# ionode.net
KiCad netlist of a schematic drawn in EAGLE
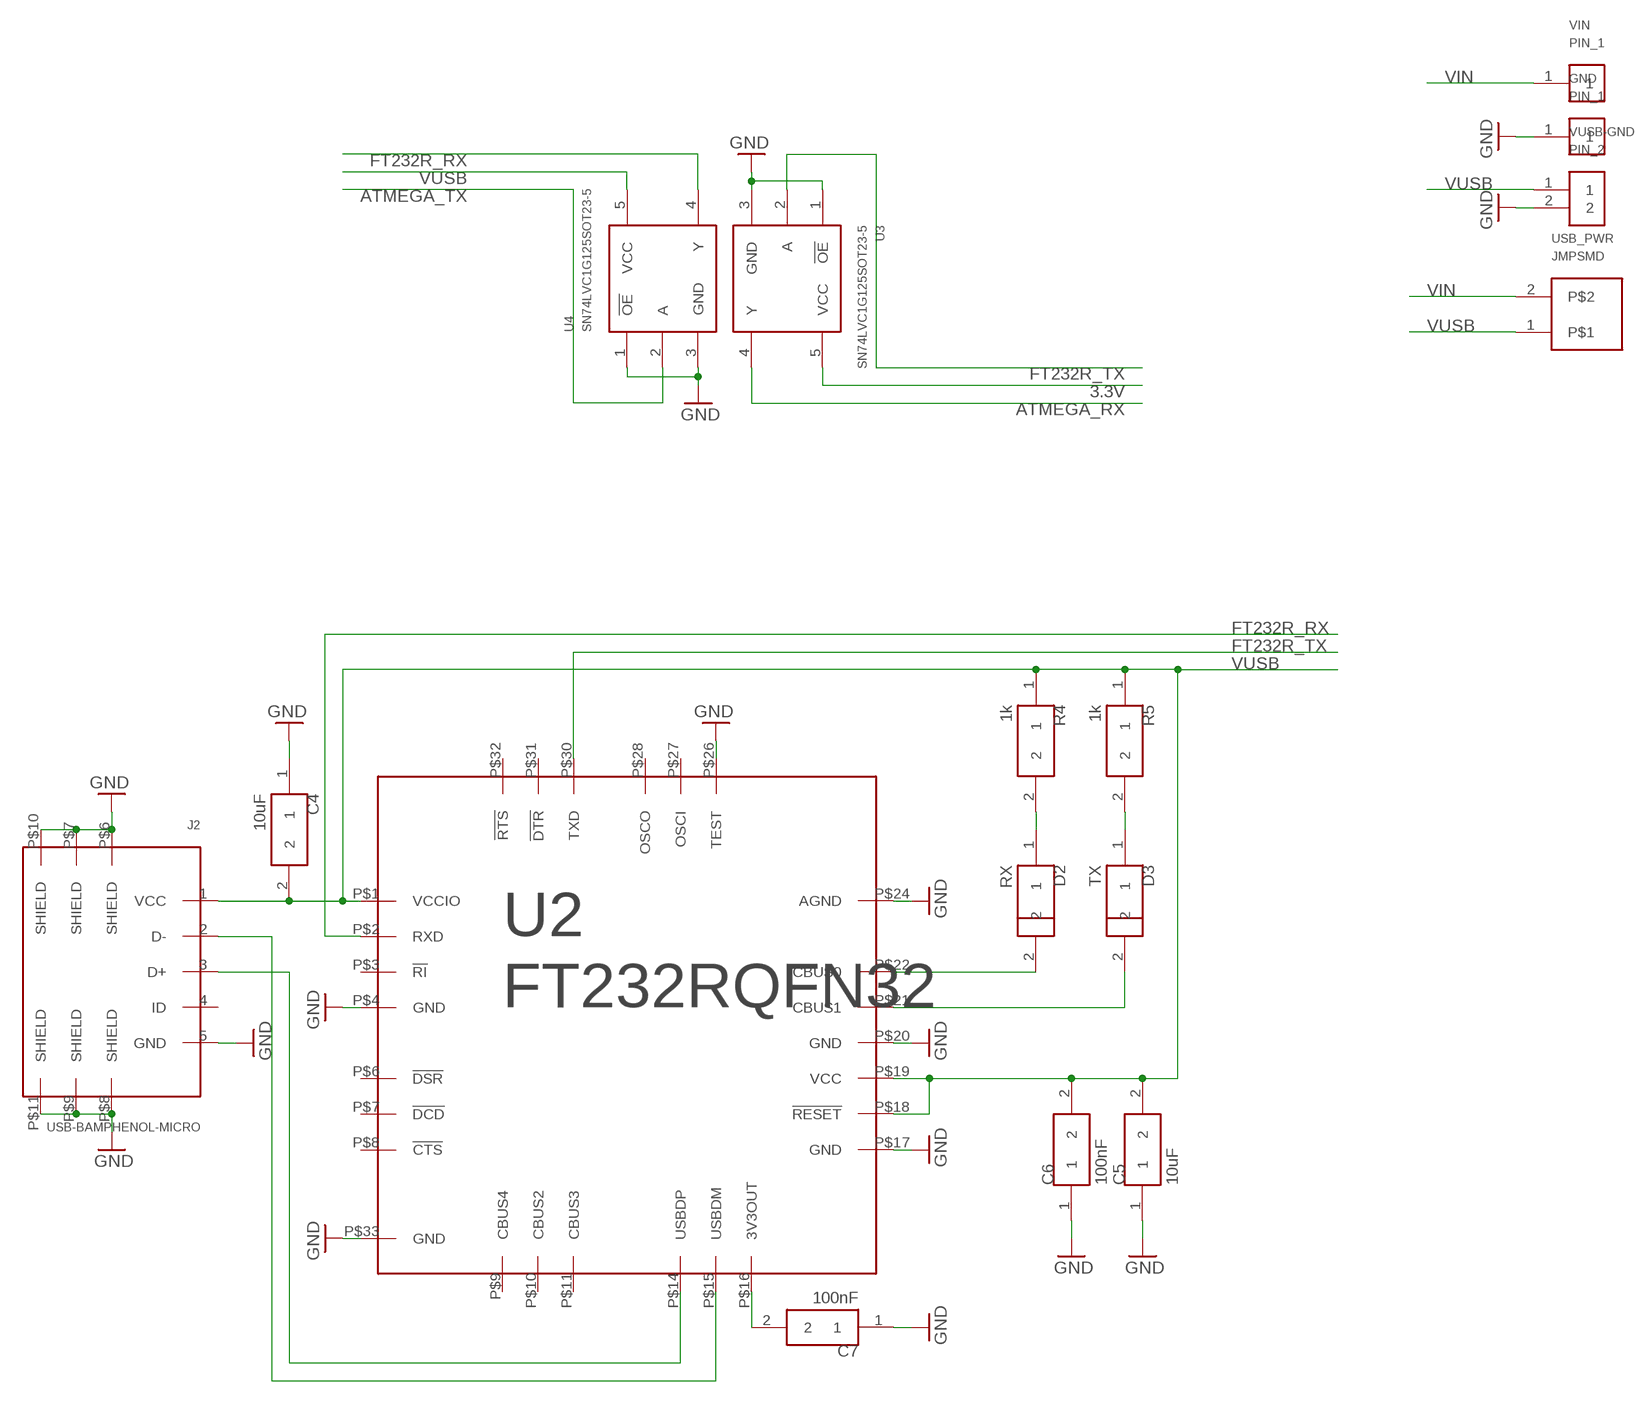
[diagram p0: schematic, sheet 1, part 1 of 2]
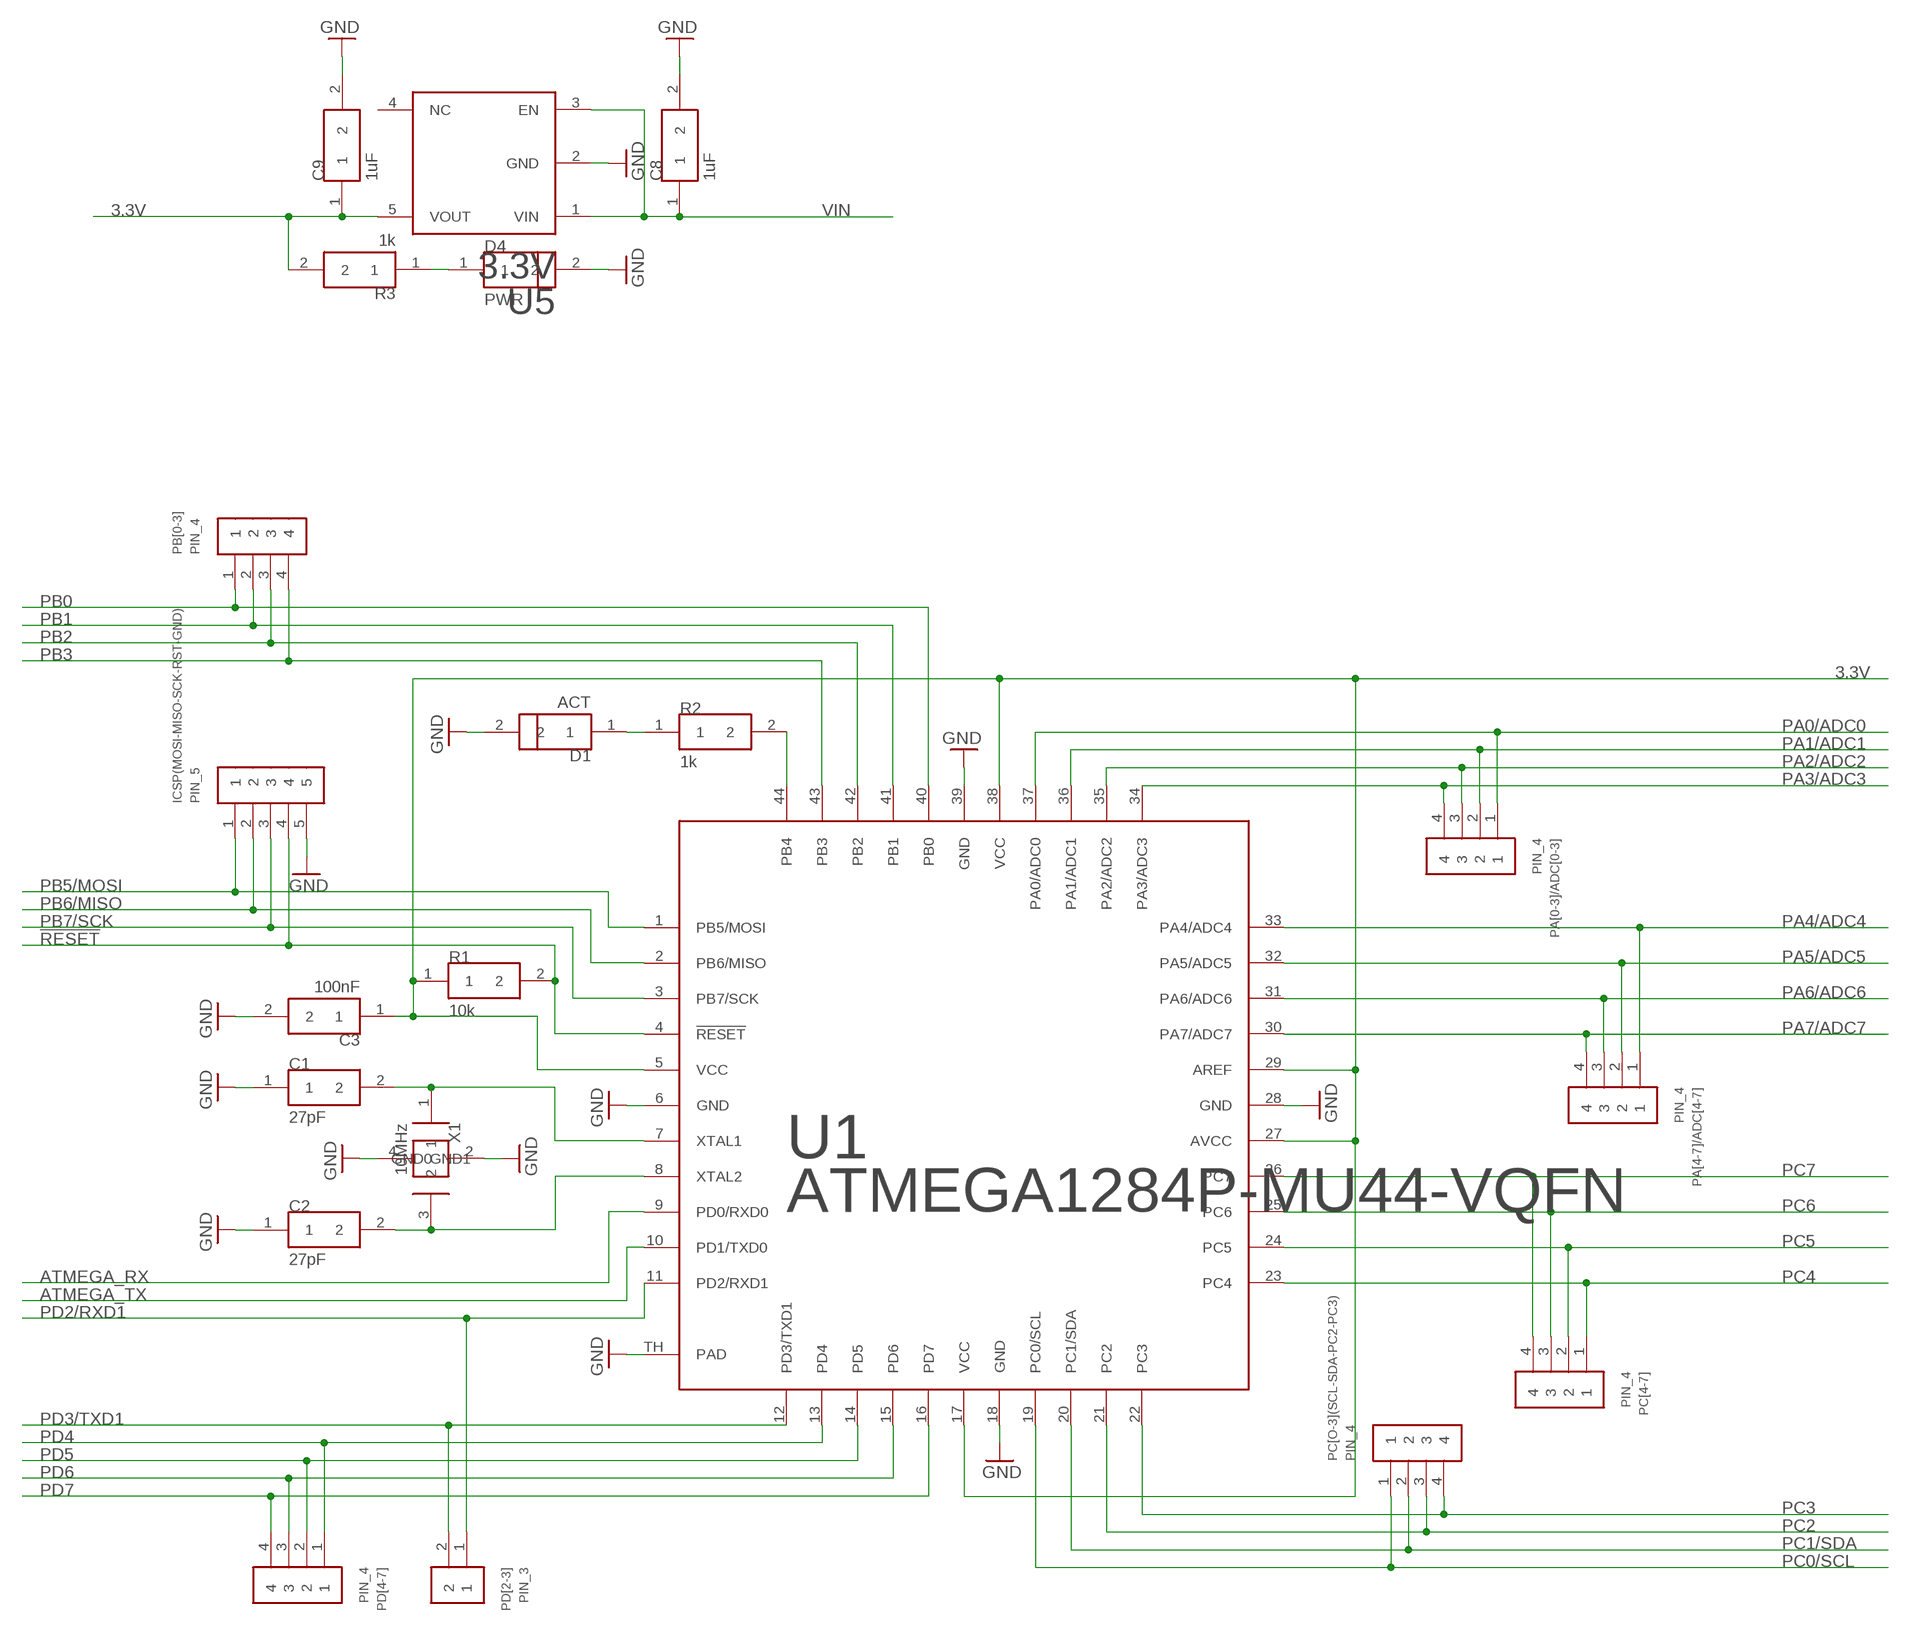
[diagram p1: schematic, sheet 1, part 2 of 2]

(export (version "E")
  (design (tool "Eeschema 10.0.6"))
  (components
    (comp (ref "C1")
      (value "27pF")
      (footprint "eagle-import:0402")
      (libsource (lib "eagle-import") (part "CAP0402"))
    )
    (comp (ref "C2")
      (value "27pF")
      (footprint "eagle-import:0402")
      (libsource (lib "eagle-import") (part "CAP0402"))
    )
    (comp (ref "C3")
      (value "100nF")
      (footprint "eagle-import:0402")
      (libsource (lib "eagle-import") (part "CAP0402"))
    )
    (comp (ref "C4")
      (value "10uF")
      (footprint "eagle-import:0805")
      (libsource (lib "eagle-import") (part "CAP0805"))
    )
    (comp (ref "C5")
      (value "10uF")
      (footprint "eagle-import:0805")
      (libsource (lib "eagle-import") (part "CAP0805"))
    )
    (comp (ref "C6")
      (value "100nF")
      (footprint "eagle-import:0402")
      (libsource (lib "eagle-import") (part "CAP0402"))
    )
    (comp (ref "C7")
      (value "100nF")
      (footprint "eagle-import:0402")
      (libsource (lib "eagle-import") (part "CAP0402"))
    )
    (comp (ref "C8")
      (value "1uF")
      (footprint "eagle-import:0402")
      (libsource (lib "eagle-import") (part "CAP0402"))
    )
    (comp (ref "C9")
      (value "1uF")
      (footprint "eagle-import:0402")
      (libsource (lib "eagle-import") (part "CAP0402"))
    )
    (comp (ref "D1")
      (value "ACT")
      (footprint "eagle-import:0402")
      (libsource (lib "eagle-import") (part "LED0402"))
    )
    (comp (ref "D2")
      (value "RX")
      (footprint "eagle-import:0402")
      (libsource (lib "eagle-import") (part "LED0402"))
    )
    (comp (ref "D3")
      (value "TX")
      (footprint "eagle-import:0402")
      (libsource (lib "eagle-import") (part "LED0402"))
    )
    (comp (ref "D4")
      (value "PWR")
      (footprint "eagle-import:0402")
      (libsource (lib "eagle-import") (part "LED0402"))
    )
    (comp (ref "GND")
      (value "PIN_1")
      (footprint "eagle-import:PIN_1")
      (libsource (lib "eagle-import") (part "PIN_1"))
    )
    (comp (ref "ICSP(MOSI-MISO-SCK-RST-GND)")
      (value "PIN_5")
      (footprint "eagle-import:PIN_5")
      (libsource (lib "eagle-import") (part "PIN_5"))
    )
    (comp (ref "J2")
      (value "USB-BAMPHENOL-MICRO")
      (footprint "eagle-import:AMPHENOL-USB-MICRO-B")
      (libsource (lib "eagle-import") (part "USB-BAMPHENOL-MICRO"))
    )
    (comp (ref "PA[0-3]/ADC[0-3]")
      (value "PIN_4")
      (footprint "eagle-import:PIN_4")
      (libsource (lib "eagle-import") (part "PIN_4"))
    )
    (comp (ref "PA[4-7]/ADC[4-7]")
      (value "PIN_4")
      (footprint "eagle-import:PIN_4")
      (libsource (lib "eagle-import") (part "PIN_4"))
    )
    (comp (ref "PB[0-3]")
      (value "PIN_4")
      (footprint "eagle-import:PIN_4")
      (libsource (lib "eagle-import") (part "PIN_4"))
    )
    (comp (ref "PC[4-7]")
      (value "PIN_4")
      (footprint "eagle-import:PIN_4")
      (libsource (lib "eagle-import") (part "PIN_4"))
    )
    (comp (ref "PC[O-3](SCL-SDA-PC2-PC3)")
      (value "PIN_4")
      (footprint "eagle-import:PIN_4")
      (libsource (lib "eagle-import") (part "PIN_4"))
    )
    (comp (ref "PD[4-7]")
      (value "PIN_4")
      (footprint "eagle-import:PIN_4")
      (libsource (lib "eagle-import") (part "PIN_4"))
    )
    (comp (ref "PIN_3")
      (value "PD[2-3]")
      (footprint "eagle-import:PIN_2")
      (libsource (lib "eagle-import") (part "PIN_2"))
    )
    (comp (ref "R1")
      (value "10k")
      (footprint "eagle-import:0402")
      (libsource (lib "eagle-import") (part "RES0402"))
    )
    (comp (ref "R2")
      (value "1k")
      (footprint "eagle-import:0402")
      (libsource (lib "eagle-import") (part "RES0402"))
    )
    (comp (ref "R3")
      (value "1k")
      (footprint "eagle-import:0402")
      (libsource (lib "eagle-import") (part "RES0402"))
    )
    (comp (ref "R4")
      (value "1k")
      (footprint "eagle-import:0402")
      (libsource (lib "eagle-import") (part "RES0402"))
    )
    (comp (ref "R5")
      (value "1k")
      (footprint "eagle-import:0402")
      (libsource (lib "eagle-import") (part "RES0402"))
    )
    (comp (ref "U1")
      (value "ATMEGA1284P-MU44-VQFN")
      (footprint "eagle-import:44-VQFN")
      (libsource (lib "eagle-import") (part "ATMEGA1284P-MU44-VQFN"))
    )
    (comp (ref "U2")
      (value "FT232RQFN32")
      (footprint "eagle-import:32-VQFN")
      (libsource (lib "eagle-import") (part "FT232RQFN32"))
    )
    (comp (ref "U3")
      (value "SN74LVC1G125SOT23-5")
      (footprint "eagle-import:SOT23-5")
      (libsource (lib "eagle-import") (part "SN74LVC1G125SOT23-5"))
    )
    (comp (ref "U4")
      (value "SN74LVC1G125SOT23-5")
      (footprint "eagle-import:SOT23-5")
      (libsource (lib "eagle-import") (part "SN74LVC1G125SOT23-5"))
    )
    (comp (ref "U5")
      (value "3.3V")
      (footprint "eagle-import:SOT23-5")
      (libsource (lib "eagle-import") (part "LP3985SOT23-5"))
    )
    (comp (ref "USB_PWR")
      (value "JMPSMD")
      (footprint "eagle-import:SMD_JMP")
      (libsource (lib "eagle-import") (part "JMPSMD"))
    )
    (comp (ref "VIN")
      (value "PIN_1")
      (footprint "eagle-import:PIN_1")
      (libsource (lib "eagle-import") (part "PIN_1"))
    )
    (comp (ref "VUSB-GND")
      (value "PIN_2")
      (footprint "eagle-import:PIN_2")
      (libsource (lib "eagle-import") (part "PIN_2"))
    )
    (comp (ref "X1")
      (value "10MHz")
      (footprint "eagle-import:XTAL_3225")
      (libsource (lib "eagle-import") (part "XTAL_GNDSMD_3225"))
    )
  )
  (nets
    (net (code "1") (name "/3.3V") (class "Default")
      (node (ref "C3") (pin "1") (pinfunction "1_1") (pintype "bidirectional"))
      (node (ref "C9") (pin "1") (pinfunction "1_1") (pintype "bidirectional"))
      (node (ref "R1") (pin "1") (pinfunction "1_1") (pintype "bidirectional"))
      (node (ref "R3") (pin "2") (pinfunction "2_2") (pintype "bidirectional"))
      (node (ref "U1") (pin "17") (pinfunction "VCC_17") (pintype "bidirectional"))
      (node (ref "U1") (pin "27") (pinfunction "AVCC_27") (pintype "bidirectional"))
      (node (ref "U1") (pin "29") (pinfunction "AREF_29") (pintype "bidirectional"))
      (node (ref "U1") (pin "38") (pinfunction "VCC_38") (pintype "bidirectional"))
      (node (ref "U1") (pin "5") (pinfunction "VCC_5") (pintype "bidirectional"))
      (node (ref "U3") (pin "5") (pinfunction "VCC_5") (pintype "bidirectional"))
      (node (ref "U5") (pin "5") (pinfunction "VOUT_5") (pintype "bidirectional"))
    )
    (net (code "2") (name "/ATMEGA_RX") (class "Default")
      (node (ref "U1") (pin "9") (pinfunction "PD0/RXD0_9") (pintype "bidirectional"))
      (node (ref "U3") (pin "4") (pinfunction "Y_4") (pintype "bidirectional"))
    )
    (net (code "3") (name "/ATMEGA_TX") (class "Default")
      (node (ref "U1") (pin "10") (pinfunction "PD1/TXD0_10") (pintype "bidirectional"))
      (node (ref "U4") (pin "2") (pinfunction "A_2") (pintype "bidirectional"))
    )
    (net (code "4") (name "/FT232R_RX") (class "Default")
      (node (ref "U2") (pin "P$2") (pinfunction "RXD_P$2") (pintype "bidirectional"))
      (node (ref "U4") (pin "4") (pinfunction "Y_4") (pintype "bidirectional"))
    )
    (net (code "5") (name "/FT232R_TX") (class "Default")
      (node (ref "U2") (pin "P$30") (pinfunction "TXD_P$30") (pintype "bidirectional"))
      (node (ref "U3") (pin "2") (pinfunction "A_2") (pintype "bidirectional"))
    )
    (net (code "6") (name "/PA0{slash}ADC0") (class "Default")
      (node (ref "PA[0-3]/ADC[0-3]") (pin "1") (pinfunction "1_1") (pintype "bidirectional"))
      (node (ref "U1") (pin "37") (pinfunction "PA0/ADC0_37") (pintype "bidirectional"))
    )
    (net (code "7") (name "/PA1{slash}ADC1") (class "Default")
      (node (ref "PA[0-3]/ADC[0-3]") (pin "2") (pinfunction "2_2") (pintype "bidirectional"))
      (node (ref "U1") (pin "36") (pinfunction "PA1/ADC1_36") (pintype "bidirectional"))
    )
    (net (code "8") (name "/PA2{slash}ADC2") (class "Default")
      (node (ref "PA[0-3]/ADC[0-3]") (pin "3") (pinfunction "3_3") (pintype "bidirectional"))
      (node (ref "U1") (pin "35") (pinfunction "PA2/ADC2_35") (pintype "bidirectional"))
    )
    (net (code "9") (name "/PA3{slash}ADC3") (class "Default")
      (node (ref "PA[0-3]/ADC[0-3]") (pin "4") (pinfunction "4_4") (pintype "bidirectional"))
      (node (ref "U1") (pin "34") (pinfunction "PA3/ADC3_34") (pintype "bidirectional"))
    )
    (net (code "10") (name "/PA4{slash}ADC4") (class "Default")
      (node (ref "PA[4-7]/ADC[4-7]") (pin "1") (pinfunction "1_1") (pintype "bidirectional"))
      (node (ref "U1") (pin "33") (pinfunction "PA4/ADC4_33") (pintype "bidirectional"))
    )
    (net (code "11") (name "/PA5{slash}ADC5") (class "Default")
      (node (ref "PA[4-7]/ADC[4-7]") (pin "2") (pinfunction "2_2") (pintype "bidirectional"))
      (node (ref "U1") (pin "32") (pinfunction "PA5/ADC5_32") (pintype "bidirectional"))
    )
    (net (code "12") (name "/PA6{slash}ADC6") (class "Default")
      (node (ref "PA[4-7]/ADC[4-7]") (pin "3") (pinfunction "3_3") (pintype "bidirectional"))
      (node (ref "U1") (pin "31") (pinfunction "PA6/ADC6_31") (pintype "bidirectional"))
    )
    (net (code "13") (name "/PA7{slash}ADC7") (class "Default")
      (node (ref "PA[4-7]/ADC[4-7]") (pin "4") (pinfunction "4_4") (pintype "bidirectional"))
      (node (ref "U1") (pin "30") (pinfunction "PA7/ADC7_30") (pintype "bidirectional"))
    )
    (net (code "14") (name "/PB0") (class "Default")
      (node (ref "PB[0-3]") (pin "1") (pinfunction "1_1") (pintype "bidirectional"))
      (node (ref "U1") (pin "40") (pinfunction "PB0_40") (pintype "bidirectional"))
    )
    (net (code "15") (name "/PB1") (class "Default")
      (node (ref "PB[0-3]") (pin "2") (pinfunction "2_2") (pintype "bidirectional"))
      (node (ref "U1") (pin "41") (pinfunction "PB1_41") (pintype "bidirectional"))
    )
    (net (code "16") (name "/PB2") (class "Default")
      (node (ref "PB[0-3]") (pin "3") (pinfunction "3_3") (pintype "bidirectional"))
      (node (ref "U1") (pin "42") (pinfunction "PB2_42") (pintype "bidirectional"))
    )
    (net (code "17") (name "/PB3") (class "Default")
      (node (ref "PB[0-3]") (pin "4") (pinfunction "4_4") (pintype "bidirectional"))
      (node (ref "U1") (pin "43") (pinfunction "PB3_43") (pintype "bidirectional"))
    )
    (net (code "18") (name "/PB5{slash}MOSI") (class "Default")
      (node (ref "ICSP(MOSI-MISO-SCK-RST-GND)") (pin "1") (pinfunction "1_1") (pintype "bidirectional"))
      (node (ref "U1") (pin "1") (pinfunction "PB5/MOSI_1") (pintype "bidirectional"))
    )
    (net (code "19") (name "/PB6{slash}MISO") (class "Default")
      (node (ref "ICSP(MOSI-MISO-SCK-RST-GND)") (pin "2") (pinfunction "2_2") (pintype "bidirectional"))
      (node (ref "U1") (pin "2") (pinfunction "PB6/MISO_2") (pintype "bidirectional"))
    )
    (net (code "20") (name "/PB7{slash}SCK") (class "Default")
      (node (ref "ICSP(MOSI-MISO-SCK-RST-GND)") (pin "3") (pinfunction "3_3") (pintype "bidirectional"))
      (node (ref "U1") (pin "3") (pinfunction "PB7/SCK_3") (pintype "bidirectional"))
    )
    (net (code "21") (name "/PC0{slash}SCL") (class "Default")
      (node (ref "PC[O-3](SCL-SDA-PC2-PC3)") (pin "1") (pinfunction "1_1") (pintype "bidirectional"))
      (node (ref "U1") (pin "19") (pinfunction "PC0/SCL_19") (pintype "bidirectional"))
    )
    (net (code "22") (name "/PC1{slash}SDA") (class "Default")
      (node (ref "PC[O-3](SCL-SDA-PC2-PC3)") (pin "2") (pinfunction "2_2") (pintype "bidirectional"))
      (node (ref "U1") (pin "20") (pinfunction "PC1/SDA_20") (pintype "bidirectional"))
    )
    (net (code "23") (name "/PC2") (class "Default")
      (node (ref "PC[O-3](SCL-SDA-PC2-PC3)") (pin "3") (pinfunction "3_3") (pintype "bidirectional"))
      (node (ref "U1") (pin "21") (pinfunction "PC2_21") (pintype "bidirectional"))
    )
    (net (code "24") (name "/PC3") (class "Default")
      (node (ref "PC[O-3](SCL-SDA-PC2-PC3)") (pin "4") (pinfunction "4_4") (pintype "bidirectional"))
      (node (ref "U1") (pin "22") (pinfunction "PC3_22") (pintype "bidirectional"))
    )
    (net (code "25") (name "/PC4") (class "Default")
      (node (ref "PC[4-7]") (pin "1") (pinfunction "1_1") (pintype "bidirectional"))
      (node (ref "U1") (pin "23") (pinfunction "PC4_23") (pintype "bidirectional"))
    )
    (net (code "26") (name "/PC5") (class "Default")
      (node (ref "PC[4-7]") (pin "2") (pinfunction "2_2") (pintype "bidirectional"))
      (node (ref "U1") (pin "24") (pinfunction "PC5_24") (pintype "bidirectional"))
    )
    (net (code "27") (name "/PC6") (class "Default")
      (node (ref "PC[4-7]") (pin "3") (pinfunction "3_3") (pintype "bidirectional"))
      (node (ref "U1") (pin "25") (pinfunction "PC6_25") (pintype "bidirectional"))
    )
    (net (code "28") (name "/PC7") (class "Default")
      (node (ref "PC[4-7]") (pin "4") (pinfunction "4_4") (pintype "bidirectional"))
      (node (ref "U1") (pin "26") (pinfunction "PC7_26") (pintype "bidirectional"))
    )
    (net (code "29") (name "/PD2{slash}RXD1") (class "Default")
      (node (ref "PIN_3") (pin "1") (pinfunction "1_1") (pintype "bidirectional"))
      (node (ref "U1") (pin "11") (pinfunction "PD2/RXD1_11") (pintype "bidirectional"))
    )
    (net (code "30") (name "/PD3{slash}TXD1") (class "Default")
      (node (ref "PIN_3") (pin "2") (pinfunction "2_2") (pintype "bidirectional"))
      (node (ref "U1") (pin "12") (pinfunction "PD3/TXD1_12") (pintype "bidirectional"))
    )
    (net (code "31") (name "/PD4") (class "Default")
      (node (ref "PD[4-7]") (pin "1") (pinfunction "1_1") (pintype "bidirectional"))
      (node (ref "U1") (pin "13") (pinfunction "PD4_13") (pintype "bidirectional"))
    )
    (net (code "32") (name "/PD5") (class "Default")
      (node (ref "PD[4-7]") (pin "2") (pinfunction "2_2") (pintype "bidirectional"))
      (node (ref "U1") (pin "14") (pinfunction "PD5_14") (pintype "bidirectional"))
    )
    (net (code "33") (name "/PD6") (class "Default")
      (node (ref "PD[4-7]") (pin "3") (pinfunction "3_3") (pintype "bidirectional"))
      (node (ref "U1") (pin "15") (pinfunction "PD6_15") (pintype "bidirectional"))
    )
    (net (code "34") (name "/PD7") (class "Default")
      (node (ref "PD[4-7]") (pin "4") (pinfunction "4_4") (pintype "bidirectional"))
      (node (ref "U1") (pin "16") (pinfunction "PD7_16") (pintype "bidirectional"))
    )
    (net (code "35") (name "/VIN") (class "Default")
      (node (ref "C8") (pin "1") (pinfunction "1_1") (pintype "bidirectional"))
      (node (ref "U5") (pin "1") (pinfunction "VIN_1") (pintype "bidirectional"))
      (node (ref "U5") (pin "3") (pinfunction "EN_3") (pintype "bidirectional"))
      (node (ref "USB_PWR") (pin "2") (pinfunction "P$2_2") (pintype "bidirectional"))
      (node (ref "VIN") (pin "1") (pinfunction "1_1") (pintype "bidirectional"))
    )
    (net (code "36") (name "/VUSB") (class "Default")
      (node (ref "C4") (pin "2") (pinfunction "2_2") (pintype "bidirectional"))
      (node (ref "C5") (pin "2") (pinfunction "2_2") (pintype "bidirectional"))
      (node (ref "C6") (pin "2") (pinfunction "2_2") (pintype "bidirectional"))
      (node (ref "J2") (pin "1") (pinfunction "VCC_1") (pintype "bidirectional"))
      (node (ref "R4") (pin "1") (pinfunction "1_1") (pintype "bidirectional"))
      (node (ref "R5") (pin "1") (pinfunction "1_1") (pintype "bidirectional"))
      (node (ref "U2") (pin "P$1") (pinfunction "VCCIO_P$1") (pintype "bidirectional"))
      (node (ref "U2") (pin "P$18") (pinfunction "~{RESET}_P$18") (pintype "bidirectional"))
      (node (ref "U2") (pin "P$19") (pinfunction "VCC_P$19") (pintype "bidirectional"))
      (node (ref "U4") (pin "5") (pinfunction "VCC_5") (pintype "bidirectional"))
      (node (ref "USB_PWR") (pin "1") (pinfunction "P$1_1") (pintype "bidirectional"))
      (node (ref "VUSB-GND") (pin "1") (pinfunction "1_1") (pintype "bidirectional"))
    )
    (net (code "37") (name "/~{RESET}") (class "Default")
      (node (ref "ICSP(MOSI-MISO-SCK-RST-GND)") (pin "4") (pinfunction "4_4") (pintype "bidirectional"))
      (node (ref "R1") (pin "2") (pinfunction "2_2") (pintype "bidirectional"))
      (node (ref "U1") (pin "4") (pinfunction "~{RESET}_4") (pintype "bidirectional"))
    )
    (net (code "38") (name "GND") (class "Default")
      (node (ref "C1") (pin "1") (pinfunction "1_1") (pintype "bidirectional"))
      (node (ref "C2") (pin "1") (pinfunction "1_1") (pintype "bidirectional"))
      (node (ref "C3") (pin "2") (pinfunction "2_2") (pintype "bidirectional"))
      (node (ref "C4") (pin "1") (pinfunction "1_1") (pintype "bidirectional"))
      (node (ref "C5") (pin "1") (pinfunction "1_1") (pintype "bidirectional"))
      (node (ref "C6") (pin "1") (pinfunction "1_1") (pintype "bidirectional"))
      (node (ref "C7") (pin "1") (pinfunction "1_1") (pintype "bidirectional"))
      (node (ref "C8") (pin "2") (pinfunction "2_2") (pintype "bidirectional"))
      (node (ref "C9") (pin "2") (pinfunction "2_2") (pintype "bidirectional"))
      (node (ref "D1") (pin "2") (pinfunction "2_2") (pintype "bidirectional"))
      (node (ref "D4") (pin "2") (pinfunction "2_2") (pintype "bidirectional"))
      (node (ref "GND") (pin "1") (pinfunction "1_1") (pintype "bidirectional"))
      (node (ref "ICSP(MOSI-MISO-SCK-RST-GND)") (pin "5") (pinfunction "5_5") (pintype "bidirectional"))
      (node (ref "J2") (pin "5") (pinfunction "GND_5") (pintype "bidirectional"))
      (node (ref "J2") (pin "P$10") (pinfunction "SHIELD_P$10") (pintype "bidirectional"))
      (node (ref "J2") (pin "P$11") (pinfunction "SHIELD_P$11") (pintype "bidirectional"))
      (node (ref "J2") (pin "P$6") (pinfunction "SHIELD_P$6") (pintype "bidirectional"))
      (node (ref "J2") (pin "P$7") (pinfunction "SHIELD_P$7") (pintype "bidirectional"))
      (node (ref "J2") (pin "P$8") (pinfunction "SHIELD_P$8") (pintype "bidirectional"))
      (node (ref "J2") (pin "P$9") (pinfunction "SHIELD_P$9") (pintype "bidirectional"))
      (node (ref "U1") (pin "18") (pinfunction "GND_18") (pintype "bidirectional"))
      (node (ref "U1") (pin "28") (pinfunction "GND_28") (pintype "bidirectional"))
      (node (ref "U1") (pin "39") (pinfunction "GND_39") (pintype "bidirectional"))
      (node (ref "U1") (pin "6") (pinfunction "GND_6") (pintype "bidirectional"))
      (node (ref "U1") (pin "TH") (pinfunction "PAD_TH") (pintype "bidirectional"))
      (node (ref "U2") (pin "P$17") (pinfunction "GND_P$17") (pintype "bidirectional"))
      (node (ref "U2") (pin "P$20") (pinfunction "GND_P$20") (pintype "bidirectional"))
      (node (ref "U2") (pin "P$24") (pinfunction "AGND_P$24") (pintype "bidirectional"))
      (node (ref "U2") (pin "P$26") (pinfunction "TEST_P$26") (pintype "bidirectional"))
      (node (ref "U2") (pin "P$33") (pinfunction "GND_P$33") (pintype "bidirectional"))
      (node (ref "U2") (pin "P$4") (pinfunction "GND_P$4") (pintype "bidirectional"))
      (node (ref "U3") (pin "1") (pinfunction "~{OE}_1") (pintype "bidirectional"))
      (node (ref "U3") (pin "3") (pinfunction "GND_3") (pintype "bidirectional"))
      (node (ref "U4") (pin "1") (pinfunction "~{OE}_1") (pintype "bidirectional"))
      (node (ref "U4") (pin "3") (pinfunction "GND_3") (pintype "bidirectional"))
      (node (ref "U5") (pin "2") (pinfunction "GND_2") (pintype "bidirectional"))
      (node (ref "VUSB-GND") (pin "2") (pinfunction "2_2") (pintype "bidirectional"))
      (node (ref "X1") (pin "2") (pinfunction "GND0_2") (pintype "bidirectional"))
      (node (ref "X1") (pin "4") (pinfunction "GND1_4") (pintype "bidirectional"))
    )
    (net (code "39") (name "Net-(D1-Pad1)") (class "Default")
      (node (ref "D1") (pin "1") (pinfunction "1_1") (pintype "bidirectional"))
      (node (ref "R2") (pin "1") (pinfunction "1_1") (pintype "bidirectional"))
    )
    (net (code "40") (name "Net-(D2-Pad1)") (class "Default")
      (node (ref "D2") (pin "1") (pinfunction "1_1") (pintype "bidirectional"))
      (node (ref "R4") (pin "2") (pinfunction "2_2") (pintype "bidirectional"))
    )
    (net (code "41") (name "Net-(D3-Pad1)") (class "Default")
      (node (ref "D3") (pin "1") (pinfunction "1_1") (pintype "bidirectional"))
      (node (ref "R5") (pin "2") (pinfunction "2_2") (pintype "bidirectional"))
    )
    (net (code "42") (name "Net-(D4-Pad1)") (class "Default")
      (node (ref "D4") (pin "1") (pinfunction "1_1") (pintype "bidirectional"))
      (node (ref "R3") (pin "1") (pinfunction "1_1") (pintype "bidirectional"))
    )
    (net (code "43") (name "Net-(J2-D+)") (class "Default")
      (node (ref "J2") (pin "3") (pinfunction "D+_3") (pintype "bidirectional"))
      (node (ref "U2") (pin "P$14") (pinfunction "USBDP_P$14") (pintype "bidirectional"))
    )
    (net (code "44") (name "Net-(J2-D-)") (class "Default")
      (node (ref "J2") (pin "2") (pinfunction "D-_2") (pintype "bidirectional"))
      (node (ref "U2") (pin "P$15") (pinfunction "USBDM_P$15") (pintype "bidirectional"))
    )
    (net (code "45") (name "Net-(U1-PB4)") (class "Default")
      (node (ref "R2") (pin "2") (pinfunction "2_2") (pintype "bidirectional"))
      (node (ref "U1") (pin "44") (pinfunction "PB4_44") (pintype "bidirectional"))
    )
    (net (code "46") (name "Net-(U1-XTAL1)") (class "Default")
      (node (ref "C1") (pin "2") (pinfunction "2_2") (pintype "bidirectional"))
      (node (ref "U1") (pin "7") (pinfunction "XTAL1_7") (pintype "bidirectional"))
      (node (ref "X1") (pin "1") (pinfunction "1_1") (pintype "bidirectional"))
    )
    (net (code "47") (name "Net-(U1-XTAL2)") (class "Default")
      (node (ref "C2") (pin "2") (pinfunction "2_2") (pintype "bidirectional"))
      (node (ref "U1") (pin "8") (pinfunction "XTAL2_8") (pintype "bidirectional"))
      (node (ref "X1") (pin "3") (pinfunction "2_3") (pintype "bidirectional"))
    )
    (net (code "48") (name "Net-(U2-3V3OUT)") (class "Default")
      (node (ref "C7") (pin "2") (pinfunction "2_2") (pintype "bidirectional"))
      (node (ref "U2") (pin "P$16") (pinfunction "3V3OUT_P$16") (pintype "bidirectional"))
    )
    (net (code "49") (name "Net-(U2-CBUS0)") (class "Default")
      (node (ref "D2") (pin "2") (pinfunction "2_2") (pintype "bidirectional"))
      (node (ref "U2") (pin "P$22") (pinfunction "CBUS0_P$22") (pintype "bidirectional"))
    )
    (net (code "50") (name "Net-(U2-CBUS1)") (class "Default")
      (node (ref "D3") (pin "2") (pinfunction "2_2") (pintype "bidirectional"))
      (node (ref "U2") (pin "P$21") (pinfunction "CBUS1_P$21") (pintype "bidirectional"))
    )
    (net (code "51") (name "unconnected-(J2-ID-Pad4)") (class "Default")
      (node (ref "J2") (pin "4") (pinfunction "ID_4") (pintype "bidirectional"))
    )
    (net (code "52") (name "unconnected-(U2-CBUS2-PadP$10)") (class "Default")
      (node (ref "U2") (pin "P$10") (pinfunction "CBUS2_P$10") (pintype "bidirectional"))
    )
    (net (code "53") (name "unconnected-(U2-CBUS3-PadP$11)") (class "Default")
      (node (ref "U2") (pin "P$11") (pinfunction "CBUS3_P$11") (pintype "bidirectional"))
    )
    (net (code "54") (name "unconnected-(U2-CBUS4-PadP$9)") (class "Default")
      (node (ref "U2") (pin "P$9") (pinfunction "CBUS4_P$9") (pintype "bidirectional"))
    )
    (net (code "55") (name "unconnected-(U2-OSCI-PadP$27)") (class "Default")
      (node (ref "U2") (pin "P$27") (pinfunction "OSCI_P$27") (pintype "bidirectional"))
    )
    (net (code "56") (name "unconnected-(U2-OSCO-PadP$28)") (class "Default")
      (node (ref "U2") (pin "P$28") (pinfunction "OSCO_P$28") (pintype "bidirectional"))
    )
    (net (code "57") (name "unconnected-(U2-~{CTS}-PadP$8)") (class "Default")
      (node (ref "U2") (pin "P$8") (pinfunction "~{CTS}_P$8") (pintype "bidirectional"))
    )
    (net (code "58") (name "unconnected-(U2-~{DCD}-PadP$7)") (class "Default")
      (node (ref "U2") (pin "P$7") (pinfunction "~{DCD}_P$7") (pintype "bidirectional"))
    )
    (net (code "59") (name "unconnected-(U2-~{DSR}-PadP$6)") (class "Default")
      (node (ref "U2") (pin "P$6") (pinfunction "~{DSR}_P$6") (pintype "bidirectional"))
    )
    (net (code "60") (name "unconnected-(U2-~{DTR}-PadP$31)") (class "Default")
      (node (ref "U2") (pin "P$31") (pinfunction "~{DTR}_P$31") (pintype "bidirectional"))
    )
    (net (code "61") (name "unconnected-(U2-~{RI}-PadP$3)") (class "Default")
      (node (ref "U2") (pin "P$3") (pinfunction "~{RI}_P$3") (pintype "bidirectional"))
    )
    (net (code "62") (name "unconnected-(U2-~{RTS}-PadP$32)") (class "Default")
      (node (ref "U2") (pin "P$32") (pinfunction "~{RTS}_P$32") (pintype "bidirectional"))
    )
    (net (code "63") (name "unconnected-(U5-NC-Pad4)") (class "Default")
      (node (ref "U5") (pin "4") (pinfunction "NC_4") (pintype "bidirectional"))
    )
  )
)
